# ir-sensor-breakout-mk-2_2-smd.net
KiCad netlist of a schematic drawn in EAGLE
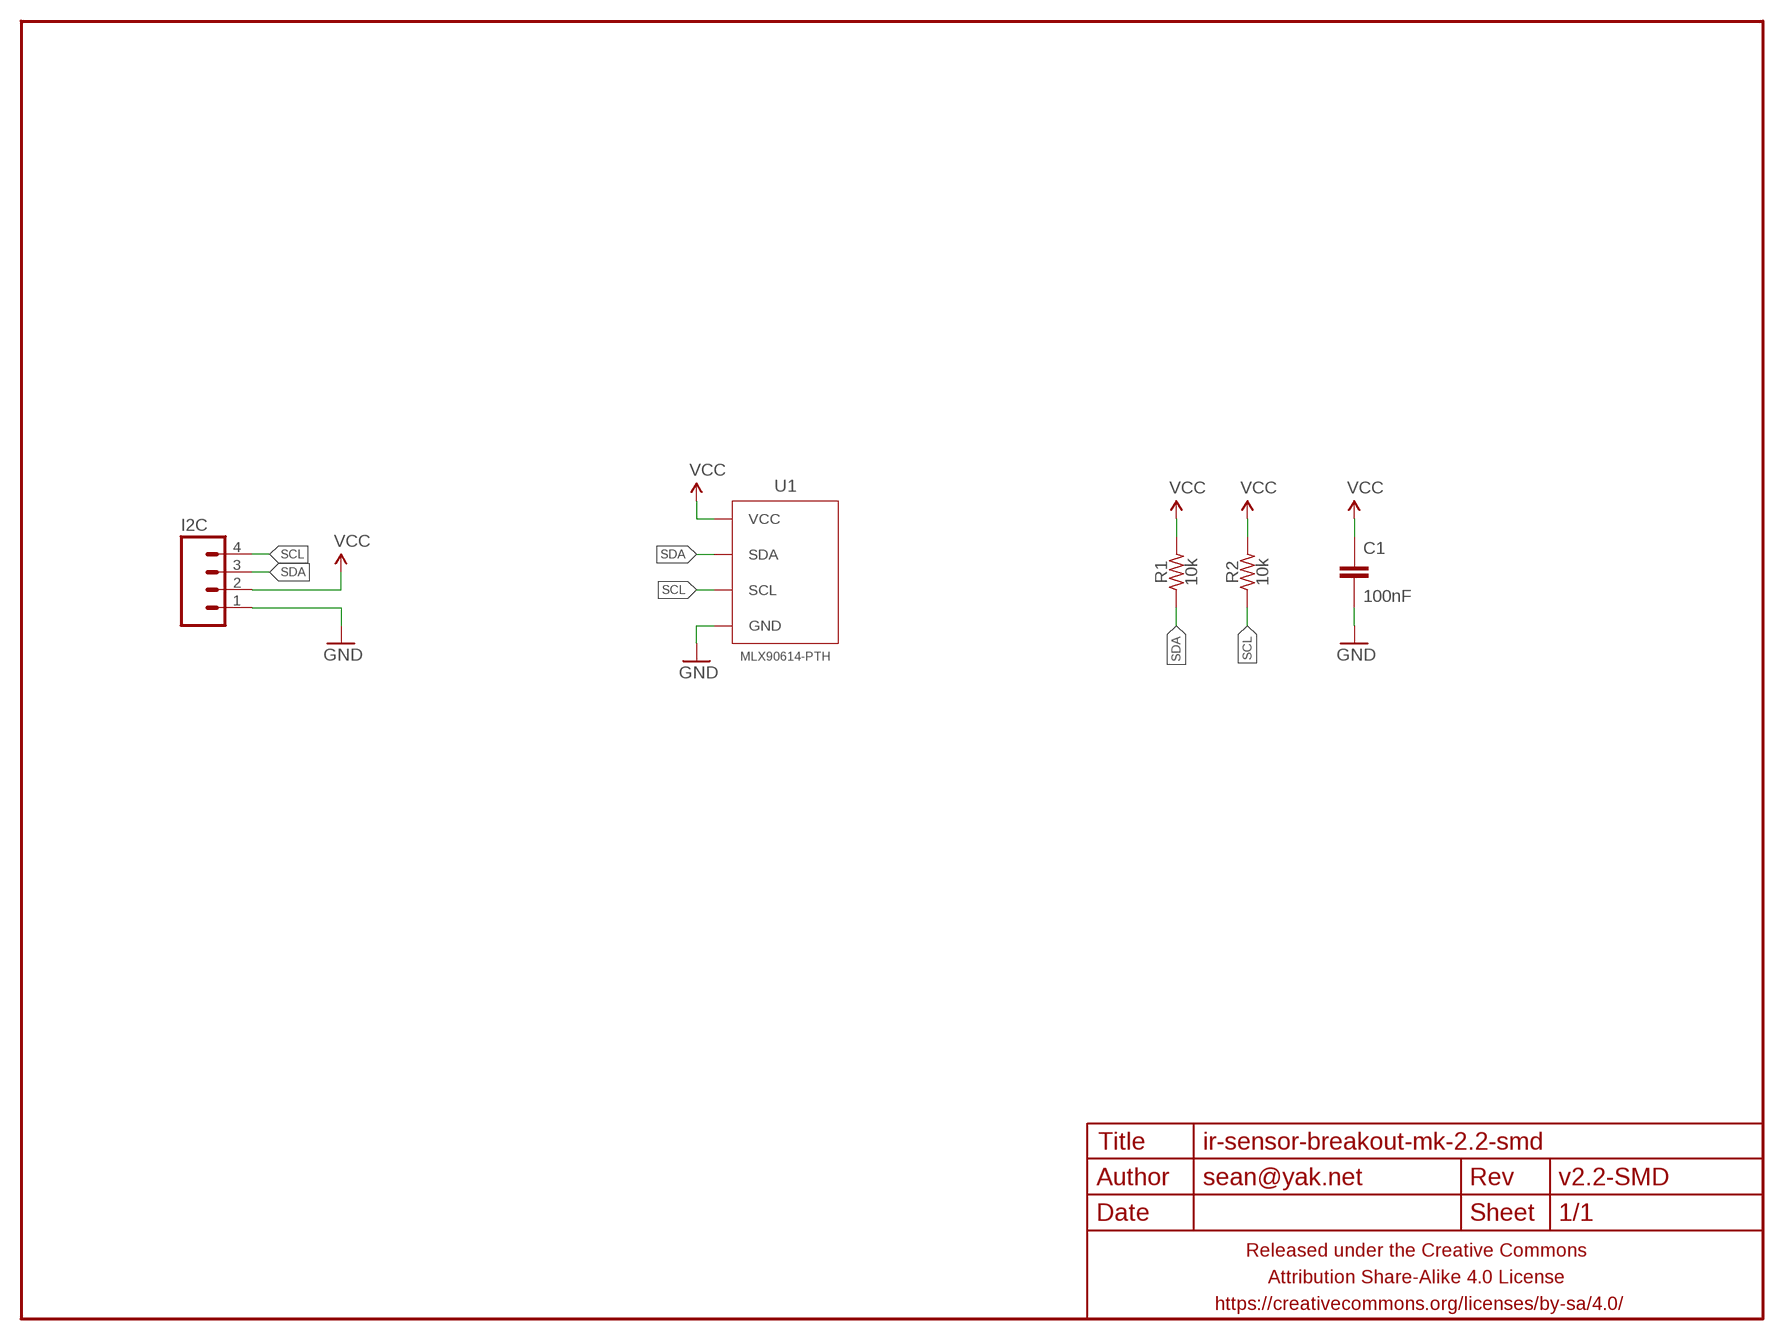
[diagram p0: schematic, sheet 1]

(export (version "E")
  (design (tool "Eeschema 10.0.6"))
  (components
    (comp (ref "C1")
      (value "100nF")
      (footprint "eagle-import:C0805")
      (libsource (lib "eagle-import") (part "CAPACITOR-CERAMICC0805"))
    )
    (comp (ref "FRAME1")
      (value "FRAME-LETTERNO_PACKAGE")
      (footprint "eagle-import:DUMMY")
      (fields (field (name "DESIGNER") "sean@yak.net") (field (name "VERSION") "v2.2-SMD"))
      (libsource (lib "eagle-import") (part "FRAME-LETTERNO_PACKAGE"))
    )
    (comp (ref "I2C")
      (value "M04JST-PTH-VERT")
      (footprint "eagle-import:JST-4-PH-VERT-PTH")
      (libsource (lib "eagle-import") (part "M04JST-PTH-VERT"))
    )
    (comp (ref "R1")
      (value "10k")
      (footprint "eagle-import:R0805")
      (libsource (lib "eagle-import") (part "RESISTORR0805"))
    )
    (comp (ref "R2")
      (value "10k")
      (footprint "eagle-import:R0805")
      (libsource (lib "eagle-import") (part "RESISTORR0805"))
    )
    (comp (ref "U1")
      (value "MLX90614-PTH")
      (footprint "eagle-import:TO-39-4")
      (libsource (lib "eagle-import") (part "MLX906145V-PTH"))
    )
  )
  (nets
    (net (code "1") (name "GND") (class "Default")
      (node (ref "C1") (pin "2") (pinfunction "2_2") (pintype "passive"))
      (node (ref "I2C") (pin "1") (pinfunction "1_1") (pintype "passive"))
      (node (ref "U1") (pin "4") (pinfunction "GND_4") (pintype "bidirectional"))
    )
    (net (code "2") (name "SCL") (class "Default")
      (node (ref "I2C") (pin "4") (pinfunction "4_4") (pintype "passive"))
      (node (ref "R2") (pin "1") (pinfunction "1_1") (pintype "passive"))
      (node (ref "U1") (pin "1") (pinfunction "SCL_1") (pintype "bidirectional"))
    )
    (net (code "3") (name "SDA") (class "Default")
      (node (ref "I2C") (pin "3") (pinfunction "3_3") (pintype "passive"))
      (node (ref "R1") (pin "1") (pinfunction "1_1") (pintype "passive"))
      (node (ref "U1") (pin "2") (pinfunction "SDA_2") (pintype "bidirectional"))
    )
    (net (code "4") (name "VCC") (class "Default")
      (node (ref "C1") (pin "1") (pinfunction "1_1") (pintype "passive"))
      (node (ref "I2C") (pin "2") (pinfunction "2_2") (pintype "passive"))
      (node (ref "R1") (pin "2") (pinfunction "2_2") (pintype "passive"))
      (node (ref "R2") (pin "2") (pinfunction "2_2") (pintype "passive"))
      (node (ref "U1") (pin "3") (pinfunction "VCC_3") (pintype "bidirectional"))
    )
  )
)
